# EEZ_DIB_PREL6_r1B2.net
KiCad netlist of a schematic drawn in EAGLE
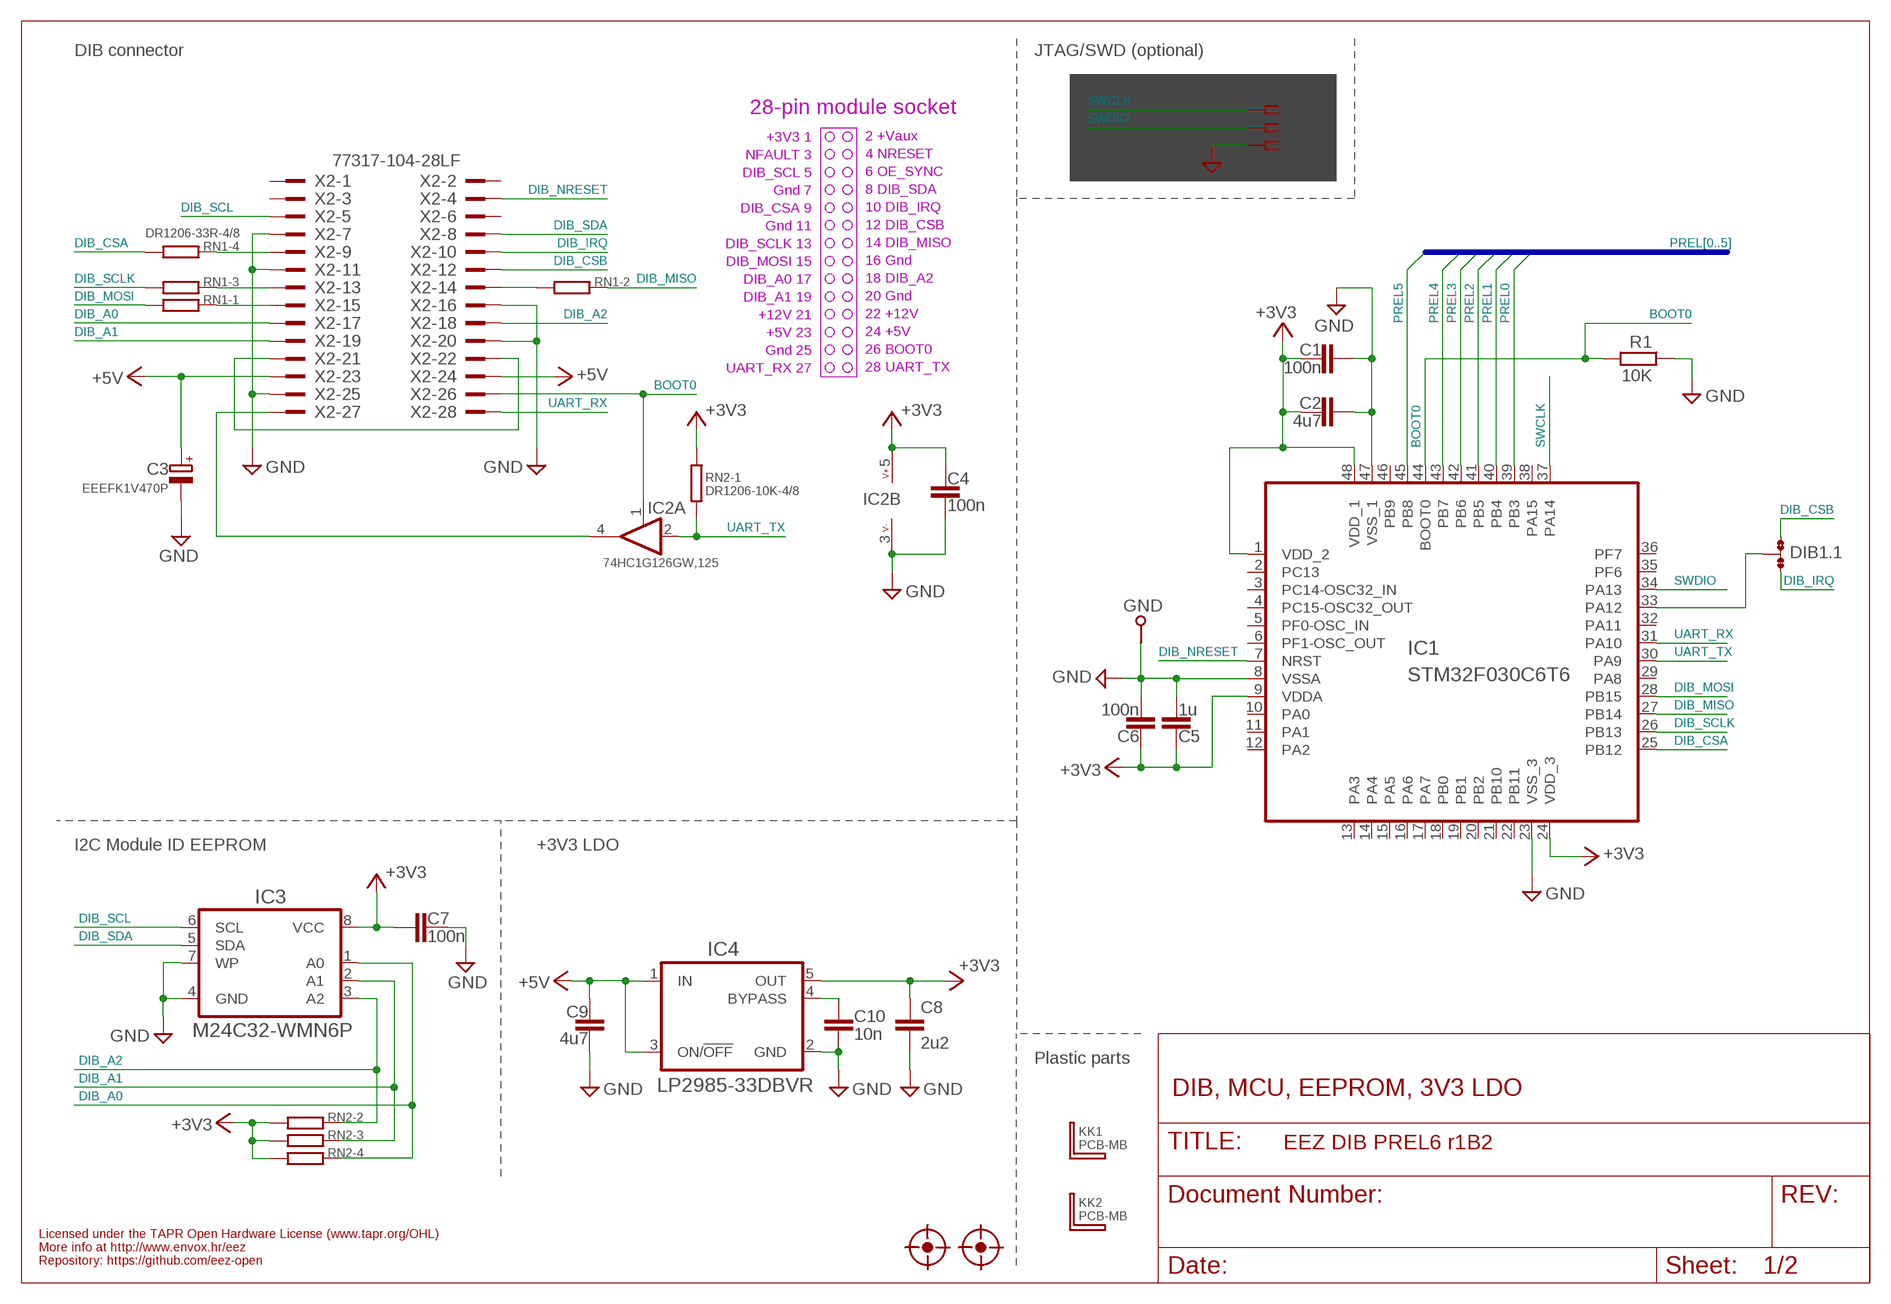
[diagram p0: schematic, sheet 1]
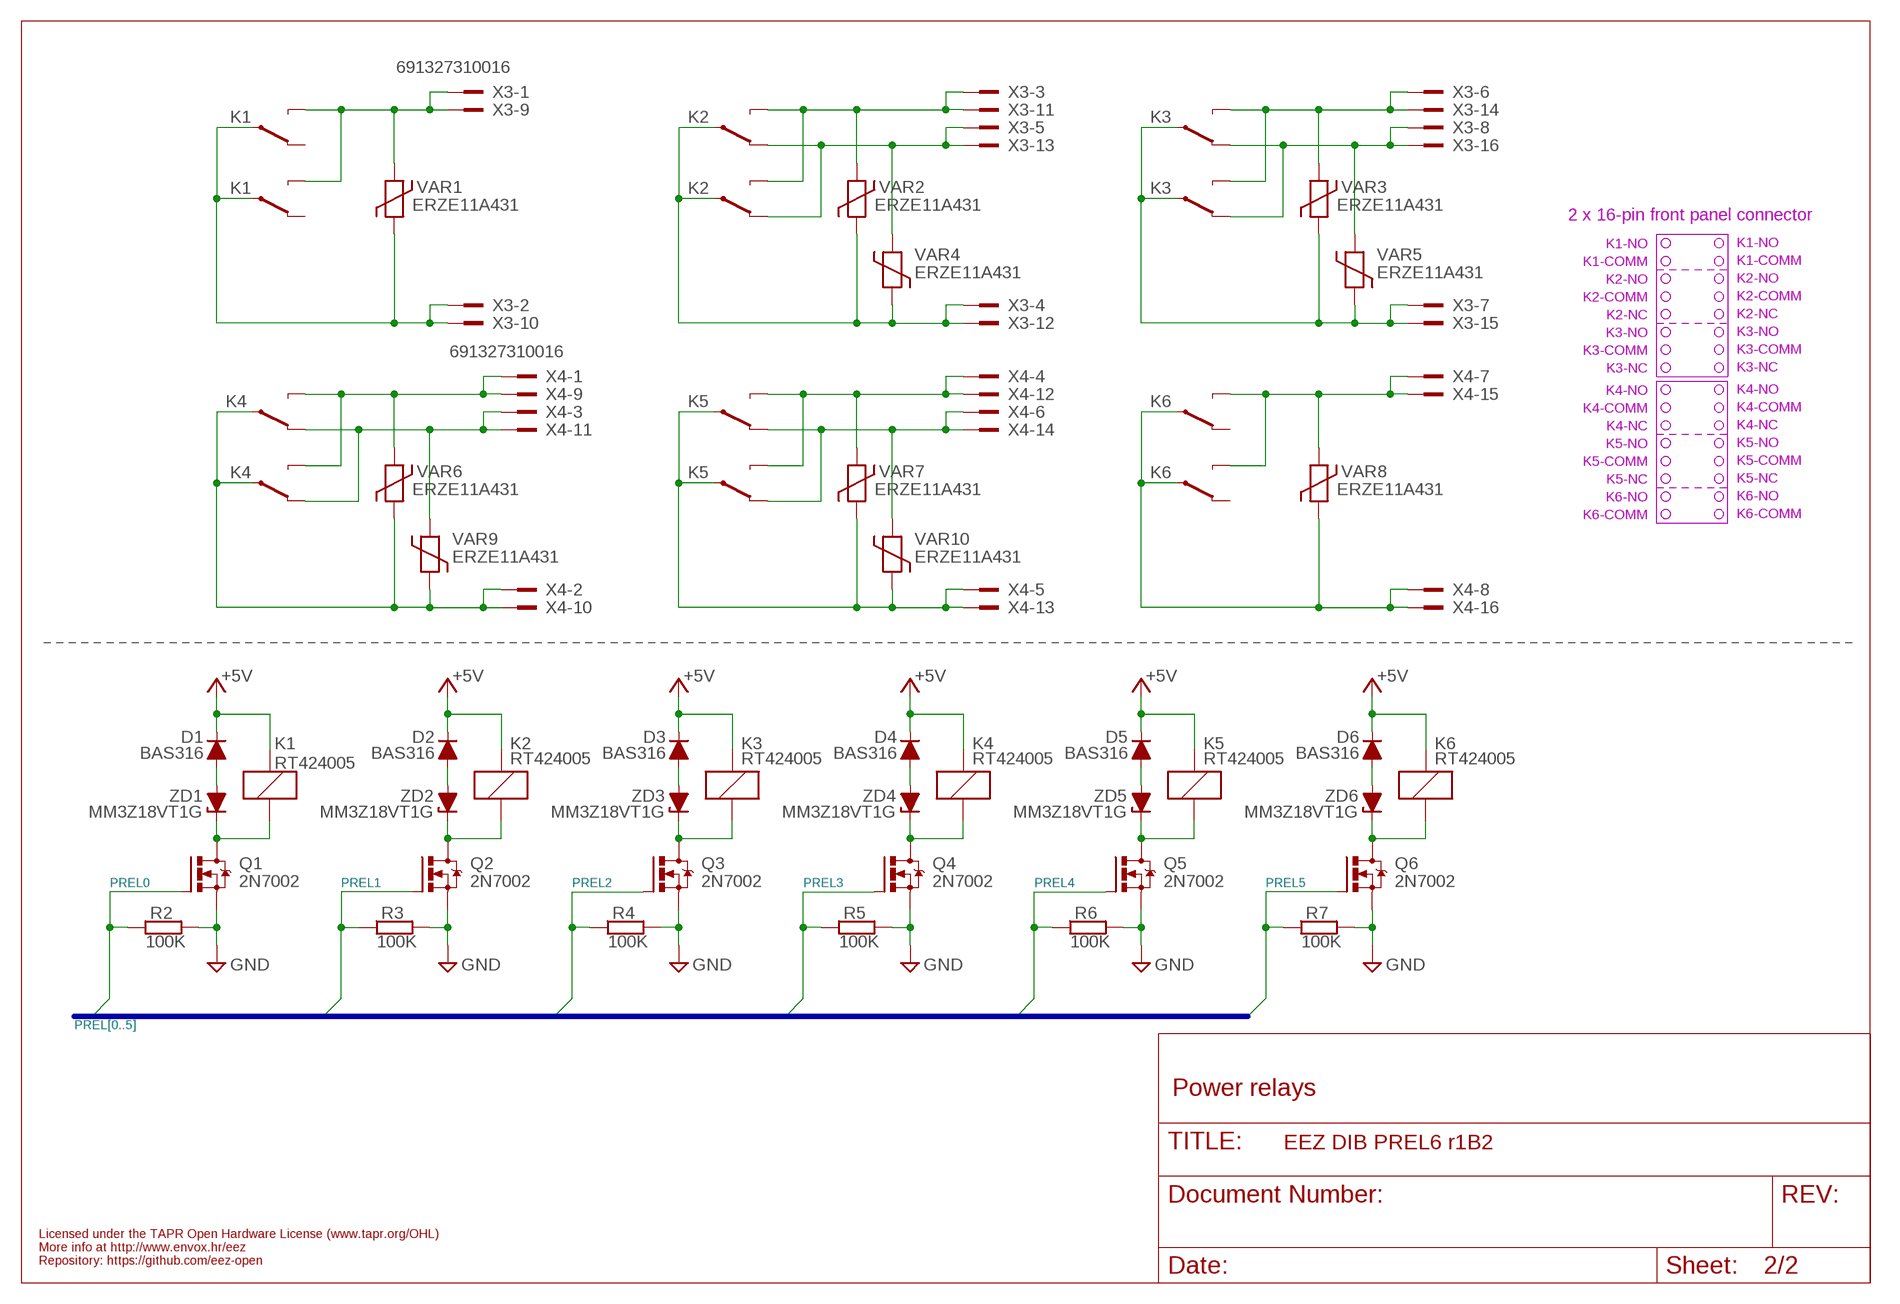
[diagram p1: schematic, sheet 2]

(export (version "E")
  (design (tool "Eeschema 10.0.6"))
  (components
    (comp (ref "D1")
      (value "BAS316")
      (footprint "eagle-import:SOD323-R")
      (libsource (lib "eagle-import") (part "DIODESOD323R"))
    )
    (comp (ref "D2")
      (value "BAS316")
      (footprint "eagle-import:SOD323-R")
      (libsource (lib "eagle-import") (part "DIODESOD323R"))
    )
    (comp (ref "D3")
      (value "BAS316")
      (footprint "eagle-import:SOD323-R")
      (libsource (lib "eagle-import") (part "DIODESOD323R"))
    )
    (comp (ref "D4")
      (value "BAS316")
      (footprint "eagle-import:SOD323-R")
      (libsource (lib "eagle-import") (part "DIODESOD323R"))
    )
    (comp (ref "D5")
      (value "BAS316")
      (footprint "eagle-import:SOD323-R")
      (libsource (lib "eagle-import") (part "DIODESOD323R"))
    )
    (comp (ref "D6")
      (value "BAS316")
      (footprint "eagle-import:SOD323-R")
      (libsource (lib "eagle-import") (part "DIODESOD323R"))
    )
    (comp (ref "K1")
      (value "RT424005")
      (footprint "eagle-import:RT-C_016A5_ROUND")
      (libsource (lib "eagle-import") (part "RELAY_RT314012-2"))
    )
    (comp (ref "K2")
      (value "RT424005")
      (footprint "eagle-import:RT-C_016A5_ROUND")
      (libsource (lib "eagle-import") (part "RELAY_RT314012-2"))
    )
    (comp (ref "K3")
      (value "RT424005")
      (footprint "eagle-import:RT-C_016A5_ROUND")
      (libsource (lib "eagle-import") (part "RELAY_RT314012-2"))
    )
    (comp (ref "K4")
      (value "RT424005")
      (footprint "eagle-import:RT-C_016A5_ROUND")
      (libsource (lib "eagle-import") (part "RELAY_RT314012-2"))
    )
    (comp (ref "K5")
      (value "RT424005")
      (footprint "eagle-import:RT-C_016A5_ROUND")
      (libsource (lib "eagle-import") (part "RELAY_RT314012-2"))
    )
    (comp (ref "K6")
      (value "RT424005")
      (footprint "eagle-import:RT-C_016A5_ROUND")
      (libsource (lib "eagle-import") (part "RELAY_RT314012-2"))
    )
    (comp (ref "Q1")
      (value "2N7002")
      (footprint "eagle-import:SOT103P240X110-3N")
      (fields
        (field (name "MPN") "2N7002-7-F")
        (field (name "MPN_1") "2N7002-7-F")
        (field (name "OC_FARNELL") "1713823")
        (field (name "OC_NEWARK") "25R5679")
        (field (name "PACKAGE") "SOT-23-3")
        (field (name "SUPPLIER") "DIODES INC.")
      )
      (libsource (lib "eagle-import") (part "2N7002"))
    )
    (comp (ref "Q2")
      (value "2N7002")
      (footprint "eagle-import:SOT103P240X110-3N")
      (fields
        (field (name "MPN") "2N7002-7-F")
        (field (name "MPN_1") "2N7002-7-F")
        (field (name "OC_FARNELL") "1713823")
        (field (name "OC_NEWARK") "25R5679")
        (field (name "PACKAGE") "SOT-23-3")
        (field (name "SUPPLIER") "DIODES INC.")
      )
      (libsource (lib "eagle-import") (part "2N7002"))
    )
    (comp (ref "Q3")
      (value "2N7002")
      (footprint "eagle-import:SOT103P240X110-3N")
      (fields
        (field (name "MPN") "2N7002-7-F")
        (field (name "MPN_1") "2N7002-7-F")
        (field (name "OC_FARNELL") "1713823")
        (field (name "OC_NEWARK") "25R5679")
        (field (name "PACKAGE") "SOT-23-3")
        (field (name "SUPPLIER") "DIODES INC.")
      )
      (libsource (lib "eagle-import") (part "2N7002"))
    )
    (comp (ref "Q4")
      (value "2N7002")
      (footprint "eagle-import:SOT103P240X110-3N")
      (fields
        (field (name "MPN") "2N7002-7-F")
        (field (name "MPN_1") "2N7002-7-F")
        (field (name "OC_FARNELL") "1713823")
        (field (name "OC_NEWARK") "25R5679")
        (field (name "PACKAGE") "SOT-23-3")
        (field (name "SUPPLIER") "DIODES INC.")
      )
      (libsource (lib "eagle-import") (part "2N7002"))
    )
    (comp (ref "Q5")
      (value "2N7002")
      (footprint "eagle-import:SOT103P240X110-3N")
      (fields
        (field (name "MPN") "2N7002-7-F")
        (field (name "MPN_1") "2N7002-7-F")
        (field (name "OC_FARNELL") "1713823")
        (field (name "OC_NEWARK") "25R5679")
        (field (name "PACKAGE") "SOT-23-3")
        (field (name "SUPPLIER") "DIODES INC.")
      )
      (libsource (lib "eagle-import") (part "2N7002"))
    )
    (comp (ref "Q6")
      (value "2N7002")
      (footprint "eagle-import:SOT103P240X110-3N")
      (fields
        (field (name "MPN") "2N7002-7-F")
        (field (name "MPN_1") "2N7002-7-F")
        (field (name "OC_FARNELL") "1713823")
        (field (name "OC_NEWARK") "25R5679")
        (field (name "PACKAGE") "SOT-23-3")
        (field (name "SUPPLIER") "DIODES INC.")
      )
      (libsource (lib "eagle-import") (part "2N7002"))
    )
    (comp (ref "R2")
      (value "100K")
      (footprint "eagle-import:R0805")
      (libsource (lib "eagle-import") (part "R-EU_R0805"))
    )
    (comp (ref "R3")
      (value "100K")
      (footprint "eagle-import:R0805")
      (libsource (lib "eagle-import") (part "R-EU_R0805"))
    )
    (comp (ref "R4")
      (value "100K")
      (footprint "eagle-import:R0805")
      (libsource (lib "eagle-import") (part "R-EU_R0805"))
    )
    (comp (ref "R5")
      (value "100K")
      (footprint "eagle-import:R0805")
      (libsource (lib "eagle-import") (part "R-EU_R0805"))
    )
    (comp (ref "R6")
      (value "100K")
      (footprint "eagle-import:R0805")
      (libsource (lib "eagle-import") (part "R-EU_R0805"))
    )
    (comp (ref "R7")
      (value "100K")
      (footprint "eagle-import:R0805")
      (libsource (lib "eagle-import") (part "R-EU_R0805"))
    )
    (comp (ref "VAR1")
      (value "ERZE11A431")
      (footprint "eagle-import:VARISTOR_13MM")
      (libsource (lib "eagle-import") (part "VARISTOR-13"))
    )
    (comp (ref "VAR2")
      (value "ERZE11A431")
      (footprint "eagle-import:VARISTOR_13MM")
      (libsource (lib "eagle-import") (part "VARISTOR-13"))
    )
    (comp (ref "VAR3")
      (value "ERZE11A431")
      (footprint "eagle-import:VARISTOR_13MM")
      (libsource (lib "eagle-import") (part "VARISTOR-13"))
    )
    (comp (ref "VAR4")
      (value "ERZE11A431")
      (footprint "eagle-import:VARISTOR_13MM")
      (libsource (lib "eagle-import") (part "VARISTOR-13"))
    )
    (comp (ref "VAR5")
      (value "ERZE11A431")
      (footprint "eagle-import:VARISTOR_13MM")
      (libsource (lib "eagle-import") (part "VARISTOR-13"))
    )
    (comp (ref "VAR6")
      (value "ERZE11A431")
      (footprint "eagle-import:VARISTOR_13MM")
      (libsource (lib "eagle-import") (part "VARISTOR-13"))
    )
    (comp (ref "VAR7")
      (value "ERZE11A431")
      (footprint "eagle-import:VARISTOR_13MM")
      (libsource (lib "eagle-import") (part "VARISTOR-13"))
    )
    (comp (ref "VAR8")
      (value "ERZE11A431")
      (footprint "eagle-import:VARISTOR_13MM")
      (libsource (lib "eagle-import") (part "VARISTOR-13"))
    )
    (comp (ref "VAR9")
      (value "ERZE11A431")
      (footprint "eagle-import:VARISTOR_13MM")
      (libsource (lib "eagle-import") (part "VARISTOR-13"))
    )
    (comp (ref "VAR10")
      (value "ERZE11A431")
      (footprint "eagle-import:VARISTOR_13MM")
      (libsource (lib "eagle-import") (part "VARISTOR-13"))
    )
    (comp (ref "X3")
      (value "691327310016")
      (footprint "eagle-import:691327310016")
      (libsource (lib "eagle-import") (part "691327310016"))
    )
    (comp (ref "X4")
      (value "691327310016")
      (footprint "eagle-import:691327310016")
      (libsource (lib "eagle-import") (part "691327310016"))
    )
    (comp (ref "ZD1")
      (value "MM3Z18VT1G")
      (footprint "eagle-import:SOD323-R")
      (libsource (lib "eagle-import") (part "ZENER-DIODESOD323R"))
    )
    (comp (ref "ZD2")
      (value "MM3Z18VT1G")
      (footprint "eagle-import:SOD323-R")
      (libsource (lib "eagle-import") (part "ZENER-DIODESOD323R"))
    )
    (comp (ref "ZD3")
      (value "MM3Z18VT1G")
      (footprint "eagle-import:SOD323-R")
      (libsource (lib "eagle-import") (part "ZENER-DIODESOD323R"))
    )
    (comp (ref "ZD4")
      (value "MM3Z18VT1G")
      (footprint "eagle-import:SOD323-R")
      (libsource (lib "eagle-import") (part "ZENER-DIODESOD323R"))
    )
    (comp (ref "ZD5")
      (value "MM3Z18VT1G")
      (footprint "eagle-import:SOD323-R")
      (libsource (lib "eagle-import") (part "ZENER-DIODESOD323R"))
    )
    (comp (ref "ZD6")
      (value "MM3Z18VT1G")
      (footprint "eagle-import:SOD323-R")
      (libsource (lib "eagle-import") (part "ZENER-DIODESOD323R"))
    )
    (comp (ref "C1")
      (value "100n")
      (footprint "eagle-import:C0603")
      (libsource (lib "eagle-import") (part "C-EUC0603"))
    )
    (comp (ref "C2")
      (value "4u7")
      (footprint "eagle-import:C0805")
      (libsource (lib "eagle-import") (part "C-EUC0805"))
    )
    (comp (ref "C3")
      (value "EEEFK1V470P")
      (footprint "eagle-import:CAPAE660X610N")
      (libsource (lib "eagle-import") (part "ECAPPANASONIC_H"))
    )
    (comp (ref "C4")
      (value "100n")
      (footprint "eagle-import:C0603")
      (libsource (lib "eagle-import") (part "C-EUC0603"))
    )
    (comp (ref "C5")
      (value "1u")
      (footprint "eagle-import:C0805")
      (libsource (lib "eagle-import") (part "C-EUC0805"))
    )
    (comp (ref "C6")
      (value "100n")
      (footprint "eagle-import:C0603")
      (libsource (lib "eagle-import") (part "C-EUC0603"))
    )
    (comp (ref "C7")
      (value "100n")
      (footprint "eagle-import:C0603")
      (libsource (lib "eagle-import") (part "C-EUC0603"))
    )
    (comp (ref "C8")
      (value "2u2")
      (footprint "eagle-import:C0805")
      (libsource (lib "eagle-import") (part "C-EUC0805"))
    )
    (comp (ref "C9")
      (value "4u7")
      (footprint "eagle-import:C0805")
      (libsource (lib "eagle-import") (part "C-EUC0805"))
    )
    (comp (ref "C10")
      (value "10n")
      (footprint "eagle-import:C0805")
      (libsource (lib "eagle-import") (part "C-EUC0805"))
    )
    (comp (ref "DIB1.1")
      (value "JP3-CUT-0805-ROTATED")
      (footprint "eagle-import:JP3-0805-CUT2")
      (libsource (lib "eagle-import") (part "JP3-CUT-0805-ROTATED"))
    )
    (comp (ref "FM1")
      (value "FIDUCIAL_2")
      (footprint "eagle-import:FIDUCIAL_DUAL")
      (libsource (lib "eagle-import") (part "FIDUCIAL_2"))
    )
    (comp (ref "FM2")
      (value "FIDUCIAL_2")
      (footprint "eagle-import:FIDUCIAL_DUAL")
      (libsource (lib "eagle-import") (part "FIDUCIAL_2"))
    )
    (comp (ref "GND")
      (value "PCB_TEST_TABSHIELD")
      (footprint "eagle-import:PCB_SHIELD_TAB")
      (libsource (lib "eagle-import") (part "PCB_TEST_TABSHIELD"))
    )
    (comp (ref "IC1")
      (value "STM32F030C6T6")
      (footprint "eagle-import:LQFP-48")
      (libsource (lib "eagle-import") (part "STM32F030C6T6"))
    )
    (comp (ref "IC2")
      (value "74HC1G126GW,125")
      (footprint "eagle-import:SOT65P210X110-5N")
      (libsource (lib "eagle-import") (part "74HC1G126GW,125"))
    )
    (comp (ref "IC3")
      (value "M24C32-WMN6P")
      (footprint "eagle-import:SOIC127P600X173-8N")
      (libsource (lib "eagle-import") (part "AT24CXXSOIC8"))
    )
    (comp (ref "IC4")
      (value "LP2985-33DBVR")
      (footprint "eagle-import:SOT95P270X145-5N")
      (libsource (lib "eagle-import") (part "LP2985"))
    )
    (comp (ref "KK1")
      (value "PCB-MB")
      (footprint "eagle-import:PCB-MB")
      (libsource (lib "eagle-import") (part "PCB-MB"))
    )
    (comp (ref "KK2")
      (value "PCB-MB")
      (footprint "eagle-import:PCB-MB")
      (libsource (lib "eagle-import") (part "PCB-MB"))
    )
    (comp (ref "R1")
      (value "10K")
      (footprint "eagle-import:R0805")
      (libsource (lib "eagle-import") (part "R-EU_R0805"))
    )
    (comp (ref "RN1")
      (value "DR1206-33R-4/8")
      (footprint "eagle-import:CAY16")
      (libsource (lib "eagle-import") (part "R_ARRAY4"))
    )
    (comp (ref "RN2")
      (value "DR1206-10K-4/8")
      (footprint "eagle-import:CAY16")
      (libsource (lib "eagle-import") (part "R_ARRAY4"))
    )
    (comp (ref "X1")
      (value "SSW-106-02-S-S")
      (footprint "eagle-import:SSW-106-02-S-S")
      (libsource (lib "eagle-import") (part "SSW-106-02-S-S"))
    )
    (comp (ref "X2")
      (value "77317-104-28LF")
      (footprint "eagle-import:77317-104-28LF")
      (libsource (lib "eagle-import") (part "77317-104-28LF"))
    )
  )
  (nets
    (net (code "1") (name "+3V3") (class "Default")
      (node (ref "C1") (pin "2") (pinfunction "2_2") (pintype "passive"))
      (node (ref "C2") (pin "1") (pinfunction "1_1") (pintype "passive"))
      (node (ref "C4") (pin "1") (pinfunction "1_1") (pintype "passive"))
      (node (ref "C5") (pin "2") (pinfunction "2_2") (pintype "passive"))
      (node (ref "C6") (pin "1") (pinfunction "1_1") (pintype "passive"))
      (node (ref "C7") (pin "2") (pinfunction "2_2") (pintype "passive"))
      (node (ref "C8") (pin "1") (pinfunction "1_1") (pintype "passive"))
      (node (ref "IC1") (pin "1") (pinfunction "VDD_2_1") (pintype "passive"))
      (node (ref "IC1") (pin "24") (pinfunction "VDD_3_24") (pintype "passive"))
      (node (ref "IC1") (pin "48") (pinfunction "VDD_1_48") (pintype "passive"))
      (node (ref "IC1") (pin "9") (pinfunction "VDDA_9") (pintype "passive"))
      (node (ref "IC2") (pin "5") (pinfunction "V+_5") (pintype "power_in"))
      (node (ref "IC3") (pin "8") (pinfunction "VCC_8") (pintype "power_in"))
      (node (ref "IC4") (pin "5") (pinfunction "OUT_5") (pintype "passive"))
      (node (ref "RN2") (pin "5") (pinfunction "2_5") (pintype "passive"))
      (node (ref "RN2") (pin "6") (pinfunction "2_6") (pintype "passive"))
      (node (ref "RN2") (pin "7") (pinfunction "2_7") (pintype "passive"))
      (node (ref "RN2") (pin "8") (pinfunction "2_8") (pintype "passive"))
    )
    (net (code "2") (name "+5V") (class "Default")
      (node (ref "C3") (pin "1") (pinfunction "+_1") (pintype "passive"))
      (node (ref "C9") (pin "2") (pinfunction "2_2") (pintype "passive"))
      (node (ref "D1") (pin "C") (pinfunction "C_C") (pintype "passive"))
      (node (ref "D2") (pin "C") (pinfunction "C_C") (pintype "passive"))
      (node (ref "D3") (pin "C") (pinfunction "C_C") (pintype "passive"))
      (node (ref "D4") (pin "C") (pinfunction "C_C") (pintype "passive"))
      (node (ref "D5") (pin "C") (pinfunction "C_C") (pintype "passive"))
      (node (ref "D6") (pin "C") (pinfunction "C_C") (pintype "passive"))
      (node (ref "IC4") (pin "1") (pinfunction "IN_1") (pintype "input"))
      (node (ref "IC4") (pin "3") (pinfunction "ON/~{OFF}_3") (pintype "input"))
      (node (ref "K1") (pin "A2") (pinfunction "C1_A2") (pintype "passive"))
      (node (ref "K2") (pin "A2") (pinfunction "C1_A2") (pintype "passive"))
      (node (ref "K3") (pin "A2") (pinfunction "C1_A2") (pintype "passive"))
      (node (ref "K4") (pin "A2") (pinfunction "C1_A2") (pintype "passive"))
      (node (ref "K5") (pin "A2") (pinfunction "C1_A2") (pintype "passive"))
      (node (ref "K6") (pin "A2") (pinfunction "C1_A2") (pintype "passive"))
      (node (ref "X2") (pin "23") (pinfunction "1_23") (pintype "passive"))
      (node (ref "X2") (pin "24") (pinfunction "1_24") (pintype "passive"))
    )
    (net (code "5") (name "BOOT0") (class "Default")
      (node (ref "IC1") (pin "44") (pinfunction "BOOT0_44") (pintype "input"))
      (node (ref "IC2") (pin "1") (pinfunction "EN_1") (pintype "input"))
      (node (ref "R1") (pin "2") (pinfunction "2_2") (pintype "passive"))
      (node (ref "X2") (pin "26") (pinfunction "1_26") (pintype "passive"))
    )
    (net (code "6") (name "DIB_A0") (class "Default")
      (node (ref "IC3") (pin "1") (pinfunction "A0_1") (pintype "input"))
      (node (ref "RN2") (pin "4") (pinfunction "1_4") (pintype "passive"))
      (node (ref "X2") (pin "17") (pinfunction "1_17") (pintype "passive"))
    )
    (net (code "7") (name "DIB_A1") (class "Default")
      (node (ref "IC3") (pin "2") (pinfunction "A1_2") (pintype "input"))
      (node (ref "RN2") (pin "3") (pinfunction "1_3") (pintype "passive"))
      (node (ref "X2") (pin "19") (pinfunction "1_19") (pintype "passive"))
    )
    (net (code "8") (name "DIB_A2") (class "Default")
      (node (ref "IC3") (pin "3") (pinfunction "A2_3") (pintype "input"))
      (node (ref "RN2") (pin "2") (pinfunction "1_2") (pintype "passive"))
      (node (ref "X2") (pin "18") (pinfunction "1_18") (pintype "passive"))
    )
    (net (code "9") (name "DIB_CSA") (class "Default")
      (node (ref "IC1") (pin "25") (pinfunction "PB12_25") (pintype "bidirectional"))
      (node (ref "RN1") (pin "4") (pinfunction "1_4") (pintype "passive"))
    )
    (net (code "10") (name "DIB_CSB") (class "Default")
      (node (ref "DIB1.1") (pin "NO") (pinfunction "NO_NO") (pintype "passive"))
      (node (ref "X2") (pin "12") (pinfunction "1_12") (pintype "passive"))
    )
    (net (code "11") (name "DIB_IRQ") (class "Default")
      (node (ref "DIB1.1") (pin "NC") (pinfunction "NC_NC") (pintype "passive"))
      (node (ref "X2") (pin "10") (pinfunction "1_10") (pintype "passive"))
    )
    (net (code "12") (name "DIB_MISO") (class "Default")
      (node (ref "IC1") (pin "27") (pinfunction "PB14_27") (pintype "bidirectional"))
      (node (ref "RN1") (pin "2") (pinfunction "1_2") (pintype "passive"))
    )
    (net (code "13") (name "DIB_MOSI") (class "Default")
      (node (ref "IC1") (pin "28") (pinfunction "PB15_28") (pintype "bidirectional"))
      (node (ref "RN1") (pin "1") (pinfunction "1_1") (pintype "passive"))
    )
    (net (code "14") (name "DIB_NRESET") (class "Default")
      (node (ref "IC1") (pin "7") (pinfunction "NRST_7") (pintype "input"))
      (node (ref "X2") (pin "4") (pinfunction "1_4") (pintype "passive"))
    )
    (net (code "15") (name "DIB_SCL") (class "Default")
      (node (ref "IC3") (pin "6") (pinfunction "SCL_6") (pintype "bidirectional"))
      (node (ref "X2") (pin "5") (pinfunction "1_5") (pintype "passive"))
    )
    (net (code "16") (name "DIB_SCLK") (class "Default")
      (node (ref "IC1") (pin "26") (pinfunction "PB13_26") (pintype "bidirectional"))
      (node (ref "RN1") (pin "3") (pinfunction "1_3") (pintype "passive"))
    )
    (net (code "17") (name "DIB_SDA") (class "Default")
      (node (ref "IC3") (pin "5") (pinfunction "SDA_5") (pintype "bidirectional"))
      (node (ref "X2") (pin "8") (pinfunction "1_8") (pintype "passive"))
    )
    (net (code "18") (name "GND") (class "Default")
      (node (ref "C1") (pin "1") (pinfunction "1_1") (pintype "passive"))
      (node (ref "C10") (pin "1") (pinfunction "1_1") (pintype "passive"))
      (node (ref "C2") (pin "2") (pinfunction "2_2") (pintype "passive"))
      (node (ref "C3") (pin "2") (pinfunction "-_2") (pintype "passive"))
      (node (ref "C4") (pin "2") (pinfunction "2_2") (pintype "passive"))
      (node (ref "C5") (pin "1") (pinfunction "1_1") (pintype "passive"))
      (node (ref "C6") (pin "2") (pinfunction "2_2") (pintype "passive"))
      (node (ref "C7") (pin "1") (pinfunction "1_1") (pintype "passive"))
      (node (ref "C8") (pin "2") (pinfunction "2_2") (pintype "passive"))
      (node (ref "C9") (pin "1") (pinfunction "1_1") (pintype "passive"))
      (node (ref "GND") (pin "1") (pinfunction "P$1_1") (pintype "bidirectional"))
      (node (ref "IC1") (pin "23") (pinfunction "VSS_3_23") (pintype "passive"))
      (node (ref "IC1") (pin "47") (pinfunction "VSS_1_47") (pintype "passive"))
      (node (ref "IC1") (pin "8") (pinfunction "VSSA_8") (pintype "passive"))
      (node (ref "IC2") (pin "3") (pinfunction "V-_3") (pintype "power_in"))
      (node (ref "IC3") (pin "4") (pinfunction "GND_4") (pintype "passive"))
      (node (ref "IC3") (pin "7") (pinfunction "WP_7") (pintype "input"))
      (node (ref "IC4") (pin "2") (pinfunction "GND_2") (pintype "passive"))
      (node (ref "Q1") (pin "2") (pinfunction "S_2") (pintype "passive"))
      (node (ref "Q2") (pin "2") (pinfunction "S_2") (pintype "passive"))
      (node (ref "Q3") (pin "2") (pinfunction "S_2") (pintype "passive"))
      (node (ref "Q4") (pin "2") (pinfunction "S_2") (pintype "passive"))
      (node (ref "Q5") (pin "2") (pinfunction "S_2") (pintype "passive"))
      (node (ref "Q6") (pin "2") (pinfunction "S_2") (pintype "passive"))
      (node (ref "R1") (pin "1") (pinfunction "1_1") (pintype "passive"))
      (node (ref "R2") (pin "2") (pinfunction "2_2") (pintype "passive"))
      (node (ref "R3") (pin "2") (pinfunction "2_2") (pintype "passive"))
      (node (ref "R4") (pin "2") (pinfunction "2_2") (pintype "passive"))
      (node (ref "R5") (pin "2") (pinfunction "2_2") (pintype "passive"))
      (node (ref "R6") (pin "2") (pinfunction "2_2") (pintype "passive"))
      (node (ref "R7") (pin "2") (pinfunction "2_2") (pintype "passive"))
      (node (ref "X1") (pin "3") (pinfunction "1_3") (pintype "passive"))
      (node (ref "X2") (pin "11") (pinfunction "1_11") (pintype "passive"))
      (node (ref "X2") (pin "16") (pinfunction "1_16") (pintype "passive"))
      (node (ref "X2") (pin "20") (pinfunction "1_20") (pintype "passive"))
      (node (ref "X2") (pin "25") (pinfunction "1_25") (pintype "passive"))
      (node (ref "X2") (pin "7") (pinfunction "1_7") (pintype "passive"))
    )
    (net (code "19") (name "Net-(D1-PadA)") (class "Default")
      (node (ref "D1") (pin "A") (pinfunction "A_A") (pintype "passive"))
      (node (ref "ZD1") (pin "A") (pinfunction "A_A") (pintype "passive"))
    )
    (net (code "20") (name "Net-(D2-PadA)") (class "Default")
      (node (ref "D2") (pin "A") (pinfunction "A_A") (pintype "passive"))
      (node (ref "ZD2") (pin "A") (pinfunction "A_A") (pintype "passive"))
    )
    (net (code "21") (name "Net-(D3-PadA)") (class "Default")
      (node (ref "D3") (pin "A") (pinfunction "A_A") (pintype "passive"))
      (node (ref "ZD3") (pin "A") (pinfunction "A_A") (pintype "passive"))
    )
    (net (code "22") (name "Net-(D4-PadA)") (class "Default")
      (node (ref "D4") (pin "A") (pinfunction "A_A") (pintype "passive"))
      (node (ref "ZD4") (pin "A") (pinfunction "A_A") (pintype "passive"))
    )
    (net (code "23") (name "Net-(D5-PadA)") (class "Default")
      (node (ref "D5") (pin "A") (pinfunction "A_A") (pintype "passive"))
      (node (ref "ZD5") (pin "A") (pinfunction "A_A") (pintype "passive"))
    )
    (net (code "24") (name "Net-(D6-PadA)") (class "Default")
      (node (ref "D6") (pin "A") (pinfunction "A_A") (pintype "passive"))
      (node (ref "ZD6") (pin "A") (pinfunction "A_A") (pintype "passive"))
    )
    (net (code "25") (name "Net-(IC1-PA12)") (class "Default")
      (node (ref "DIB1.1") (pin "COM") (pinfunction "COM_COM") (pintype "passive"))
      (node (ref "IC1") (pin "33") (pinfunction "PA12_33") (pintype "bidirectional"))
    )
    (net (code "26") (name "Net-(IC2A-O)") (class "Default")
      (node (ref "IC2") (pin "4") (pinfunction "O_4") (pintype "output"))
      (node (ref "X2") (pin "27") (pinfunction "1_27") (pintype "passive"))
    )
    (net (code "27") (name "Net-(IC4-BYPASS)") (class "Default")
      (node (ref "C10") (pin "2") (pinfunction "2_2") (pintype "passive"))
      (node (ref "IC4") (pin "4") (pinfunction "BYPASS_4") (pintype "passive"))
    )
    (net (code "28") (name "Net-(K1A-O)") (class "Default")
      (node (ref "K1") (pin "14A") (pinfunction "O_14A") (pintype "passive"))
      (node (ref "K1") (pin "14B") (pinfunction "O_14B") (pintype "passive"))
      (node (ref "VAR1") (pin "2") (pinfunction "P$2_2") (pintype "bidirectional"))
      (node (ref "X3") (pin "1") (pinfunction "1_1") (pintype "passive"))
      (node (ref "X3") (pin "9") (pinfunction "1_9") (pintype "passive"))
    )
    (net (code "29") (name "Net-(K1A-P)") (class "Default")
      (node (ref "K1") (pin "11A") (pinfunction "P_11A") (pintype "passive"))
      (node (ref "K1") (pin "11B") (pinfunction "P_11B") (pintype "passive"))
      (node (ref "VAR1") (pin "1") (pinfunction "P$1_1") (pintype "bidirectional"))
      (node (ref "X3") (pin "10") (pinfunction "1_10") (pintype "passive"))
      (node (ref "X3") (pin "2") (pinfunction "1_2") (pintype "passive"))
    )
    (net (code "30") (name "Net-(K1C-C2)") (class "Default")
      (node (ref "K1") (pin "A1") (pinfunction "C2_A1") (pintype "passive"))
      (node (ref "Q1") (pin "3") (pinfunction "D_3") (pintype "passive"))
      (node (ref "ZD1") (pin "C") (pinfunction "C_C") (pintype "passive"))
    )
    (net (code "31") (name "Net-(K2A-O)") (class "Default")
      (node (ref "K2") (pin "14A") (pinfunction "O_14A") (pintype "passive"))
      (node (ref "K2") (pin "14B") (pinfunction "O_14B") (pintype "passive"))
      (node (ref "VAR2") (pin "2") (pinfunction "P$2_2") (pintype "bidirectional"))
      (node (ref "X3") (pin "11") (pinfunction "1_11") (pintype "passive"))
      (node (ref "X3") (pin "3") (pinfunction "1_3") (pintype "passive"))
    )
    (net (code "32") (name "Net-(K2A-P)") (class "Default")
      (node (ref "K2") (pin "11A") (pinfunction "P_11A") (pintype "passive"))
      (node (ref "K2") (pin "11B") (pinfunction "P_11B") (pintype "passive"))
      (node (ref "VAR2") (pin "1") (pinfunction "P$1_1") (pintype "bidirectional"))
      (node (ref "VAR4") (pin "1") (pinfunction "P$1_1") (pintype "bidirectional"))
      (node (ref "X3") (pin "12") (pinfunction "1_12") (pintype "passive"))
      (node (ref "X3") (pin "4") (pinfunction "1_4") (pintype "passive"))
    )
    (net (code "33") (name "Net-(K2A-S)") (class "Default")
      (node (ref "K2") (pin "12A") (pinfunction "S_12A") (pintype "passive"))
      (node (ref "K2") (pin "12B") (pinfunction "S_12B") (pintype "passive"))
      (node (ref "VAR4") (pin "2") (pinfunction "P$2_2") (pintype "bidirectional"))
      (node (ref "X3") (pin "13") (pinfunction "1_13") (pintype "passive"))
      (node (ref "X3") (pin "5") (pinfunction "1_5") (pintype "passive"))
    )
    (net (code "34") (name "Net-(K2C-C2)") (class "Default")
      (node (ref "K2") (pin "A1") (pinfunction "C2_A1") (pintype "passive"))
      (node (ref "Q2") (pin "3") (pinfunction "D_3") (pintype "passive"))
      (node (ref "ZD2") (pin "C") (pinfunction "C_C") (pintype "passive"))
    )
    (net (code "35") (name "Net-(K3A-O)") (class "Default")
      (node (ref "K3") (pin "14A") (pinfunction "O_14A") (pintype "passive"))
      (node (ref "K3") (pin "14B") (pinfunction "O_14B") (pintype "passive"))
      (node (ref "VAR3") (pin "2") (pinfunction "P$2_2") (pintype "bidirectional"))
      (node (ref "X3") (pin "14") (pinfunction "1_14") (pintype "passive"))
      (node (ref "X3") (pin "6") (pinfunction "1_6") (pintype "passive"))
    )
    (net (code "36") (name "Net-(K3A-P)") (class "Default")
      (node (ref "K3") (pin "11A") (pinfunction "P_11A") (pintype "passive"))
      (node (ref "K3") (pin "11B") (pinfunction "P_11B") (pintype "passive"))
      (node (ref "VAR3") (pin "1") (pinfunction "P$1_1") (pintype "bidirectional"))
      (node (ref "VAR5") (pin "1") (pinfunction "P$1_1") (pintype "bidirectional"))
      (node (ref "X3") (pin "15") (pinfunction "1_15") (pintype "passive"))
      (node (ref "X3") (pin "7") (pinfunction "1_7") (pintype "passive"))
    )
    (net (code "37") (name "Net-(K3A-S)") (class "Default")
      (node (ref "K3") (pin "12A") (pinfunction "S_12A") (pintype "passive"))
      (node (ref "K3") (pin "12B") (pinfunction "S_12B") (pintype "passive"))
      (node (ref "VAR5") (pin "2") (pinfunction "P$2_2") (pintype "bidirectional"))
      (node (ref "X3") (pin "16") (pinfunction "1_16") (pintype "passive"))
      (node (ref "X3") (pin "8") (pinfunction "1_8") (pintype "passive"))
    )
    (net (code "38") (name "Net-(K3C-C2)") (class "Default")
      (node (ref "K3") (pin "A1") (pinfunction "C2_A1") (pintype "passive"))
      (node (ref "Q3") (pin "3") (pinfunction "D_3") (pintype "passive"))
      (node (ref "ZD3") (pin "C") (pinfunction "C_C") (pintype "passive"))
    )
    (net (code "39") (name "Net-(K4A-O)") (class "Default")
      (node (ref "K4") (pin "14A") (pinfunction "O_14A") (pintype "passive"))
      (node (ref "K4") (pin "14B") (pinfunction "O_14B") (pintype "passive"))
      (node (ref "VAR6") (pin "2") (pinfunction "P$2_2") (pintype "bidirectional"))
      (node (ref "X4") (pin "1") (pinfunction "1_1") (pintype "passive"))
      (node (ref "X4") (pin "9") (pinfunction "1_9") (pintype "passive"))
    )
    (net (code "40") (name "Net-(K4A-P)") (class "Default")
      (node (ref "K4") (pin "11A") (pinfunction "P_11A") (pintype "passive"))
      (node (ref "K4") (pin "11B") (pinfunction "P_11B") (pintype "passive"))
      (node (ref "VAR6") (pin "1") (pinfunction "P$1_1") (pintype "bidirectional"))
      (node (ref "VAR9") (pin "1") (pinfunction "P$1_1") (pintype "bidirectional"))
      (node (ref "X4") (pin "10") (pinfunction "1_10") (pintype "passive"))
      (node (ref "X4") (pin "2") (pinfunction "1_2") (pintype "passive"))
    )
    (net (code "41") (name "Net-(K4A-S)") (class "Default")
      (node (ref "K4") (pin "12A") (pinfunction "S_12A") (pintype "passive"))
      (node (ref "K4") (pin "12B") (pinfunction "S_12B") (pintype "passive"))
      (node (ref "VAR9") (pin "2") (pinfunction "P$2_2") (pintype "bidirectional"))
      (node (ref "X4") (pin "11") (pinfunction "1_11") (pintype "passive"))
      (node (ref "X4") (pin "3") (pinfunction "1_3") (pintype "passive"))
    )
    (net (code "42") (name "Net-(K4C-C2)") (class "Default")
      (node (ref "K4") (pin "A1") (pinfunction "C2_A1") (pintype "passive"))
      (node (ref "Q4") (pin "3") (pinfunction "D_3") (pintype "passive"))
      (node (ref "ZD4") (pin "C") (pinfunction "C_C") (pintype "passive"))
    )
    (net (code "43") (name "Net-(K5A-O)") (class "Default")
      (node (ref "K5") (pin "14A") (pinfunction "O_14A") (pintype "passive"))
      (node (ref "K5") (pin "14B") (pinfunction "O_14B") (pintype "passive"))
      (node (ref "VAR7") (pin "2") (pinfunction "P$2_2") (pintype "bidirectional"))
      (node (ref "X4") (pin "12") (pinfunction "1_12") (pintype "passive"))
      (node (ref "X4") (pin "4") (pinfunction "1_4") (pintype "passive"))
    )
    (net (code "44") (name "Net-(K5A-P)") (class "Default")
      (node (ref "K5") (pin "11A") (pinfunction "P_11A") (pintype "passive"))
      (node (ref "K5") (pin "11B") (pinfunction "P_11B") (pintype "passive"))
      (node (ref "VAR10") (pin "1") (pinfunction "P$1_1") (pintype "bidirectional"))
      (node (ref "VAR7") (pin "1") (pinfunction "P$1_1") (pintype "bidirectional"))
      (node (ref "X4") (pin "13") (pinfunction "1_13") (pintype "passive"))
      (node (ref "X4") (pin "5") (pinfunction "1_5") (pintype "passive"))
    )
    (net (code "45") (name "Net-(K5A-S)") (class "Default")
      (node (ref "K5") (pin "12A") (pinfunction "S_12A") (pintype "passive"))
      (node (ref "K5") (pin "12B") (pinfunction "S_12B") (pintype "passive"))
      (node (ref "VAR10") (pin "2") (pinfunction "P$2_2") (pintype "bidirectional"))
      (node (ref "X4") (pin "14") (pinfunction "1_14") (pintype "passive"))
      (node (ref "X4") (pin "6") (pinfunction "1_6") (pintype "passive"))
    )
    (net (code "46") (name "Net-(K5C-C2)") (class "Default")
      (node (ref "K5") (pin "A1") (pinfunction "C2_A1") (pintype "passive"))
      (node (ref "Q5") (pin "3") (pinfunction "D_3") (pintype "passive"))
      (node (ref "ZD5") (pin "C") (pinfunction "C_C") (pintype "passive"))
    )
    (net (code "47") (name "Net-(K6A-O)") (class "Default")
      (node (ref "K6") (pin "14A") (pinfunction "O_14A") (pintype "passive"))
      (node (ref "K6") (pin "14B") (pinfunction "O_14B") (pintype "passive"))
      (node (ref "VAR8") (pin "2") (pinfunction "P$2_2") (pintype "bidirectional"))
      (node (ref "X4") (pin "15") (pinfunction "1_15") (pintype "passive"))
      (node (ref "X4") (pin "7") (pinfunction "1_7") (pintype "passive"))
    )
    (net (code "48") (name "Net-(K6A-P)") (class "Default")
      (node (ref "K6") (pin "11A") (pinfunction "P_11A") (pintype "passive"))
      (node (ref "K6") (pin "11B") (pinfunction "P_11B") (pintype "passive"))
      (node (ref "VAR8") (pin "1") (pinfunction "P$1_1") (pintype "bidirectional"))
      (node (ref "X4") (pin "16") (pinfunction "1_16") (pintype "passive"))
      (node (ref "X4") (pin "8") (pinfunction "1_8") (pintype "passive"))
    )
    (net (code "49") (name "Net-(K6C-C2)") (class "Default")
      (node (ref "K6") (pin "A1") (pinfunction "C2_A1") (pintype "passive"))
      (node (ref "Q6") (pin "3") (pinfunction "D_3") (pintype "passive"))
      (node (ref "ZD6") (pin "C") (pinfunction "C_C") (pintype "passive"))
    )
    (net (code "50") (name "Net-(RN1A-2)") (class "Default")
      (node (ref "RN1") (pin "8") (pinfunction "2_8") (pintype "passive"))
      (node (ref "X2") (pin "15") (pinfunction "1_15") (pintype "passive"))
    )
    (net (code "51") (name "Net-(RN1B-2)") (class "Default")
      (node (ref "RN1") (pin "7") (pinfunction "2_7") (pintype "passive"))
      (node (ref "X2") (pin "14") (pinfunction "1_14") (pintype "passive"))
    )
    (net (code "52") (name "Net-(RN1C-2)") (class "Default")
      (node (ref "RN1") (pin "6") (pinfunction "2_6") (pintype "passive"))
      (node (ref "X2") (pin "13") (pinfunction "1_13") (pintype "passive"))
    )
    (net (code "53") (name "Net-(RN1D-2)") (class "Default")
      (node (ref "RN1") (pin "5") (pinfunction "2_5") (pintype "passive"))
      (node (ref "X2") (pin "9") (pinfunction "1_9") (pintype "passive"))
    )
    (net (code "54") (name "Net-(X2N-1)") (class "Default")
      (node (ref "X2") (pin "21") (pinfunction "1_21") (pintype "passive"))
      (node (ref "X2") (pin "22") (pinfunction "1_22") (pintype "passive"))
    )
    (net (code "55") (name "PREL0") (class "Default")
      (node (ref "IC1") (pin "39") (pinfunction "PB3_39") (pintype "bidirectional"))
      (node (ref "Q1") (pin "1") (pinfunction "G_1") (pintype "passive"))
      (node (ref "R2") (pin "1") (pinfunction "1_1") (pintype "passive"))
    )
    (net (code "56") (name "PREL1") (class "Default")
      (node (ref "IC1") (pin "40") (pinfunction "PB4_40") (pintype "bidirectional"))
      (node (ref "Q2") (pin "1") (pinfunction "G_1") (pintype "passive"))
      (node (ref "R3") (pin "1") (pinfunction "1_1") (pintype "passive"))
    )
    (net (code "57") (name "PREL2") (class "Default")
      (node (ref "IC1") (pin "41") (pinfunction "PB5_41") (pintype "bidirectional"))
      (node (ref "Q3") (pin "1") (pinfunction "G_1") (pintype "passive"))
      (node (ref "R4") (pin "1") (pinfunction "1_1") (pintype "passive"))
    )
    (net (code "58") (name "PREL3") (class "Default")
      (node (ref "IC1") (pin "42") (pinfunction "PB6_42") (pintype "bidirectional"))
      (node (ref "Q4") (pin "1") (pinfunction "G_1") (pintype "passive"))
      (node (ref "R5") (pin "1") (pinfunction "1_1") (pintype "passive"))
    )
    (net (code "59") (name "PREL4") (class "Default")
      (node (ref "IC1") (pin "43") (pinfunction "PB7_43") (pintype "bidirectional"))
      (node (ref "Q5") (pin "1") (pinfunction "G_1") (pintype "passive"))
      (node (ref "R6") (pin "1") (pinfunction "1_1") (pintype "passive"))
    )
    (net (code "60") (name "PREL5") (class "Default")
      (node (ref "IC1") (pin "45") (pinfunction "PB8_45") (pintype "bidirectional"))
      (node (ref "Q6") (pin "1") (pinfunction "G_1") (pintype "passive"))
      (node (ref "R7") (pin "1") (pinfunction "1_1") (pintype "passive"))
    )
    (net (code "61") (name "SWCLK") (class "Default")
      (node (ref "IC1") (pin "37") (pinfunction "PA14_37") (pintype "bidirectional"))
      (node (ref "X1") (pin "2") (pinfunction "1_2") (pintype "passive"))
    )
    (net (code "62") (name "SWDIO") (class "Default")
      (node (ref "IC1") (pin "34") (pinfunction "PA13_34") (pintype "bidirectional"))
      (node (ref "X1") (pin "4") (pinfunction "1_4") (pintype "passive"))
    )
    (net (code "63") (name "UART_RX") (class "Default")
      (node (ref "IC1") (pin "31") (pinfunction "PA10_31") (pintype "bidirectional"))
      (node (ref "X2") (pin "28") (pinfunction "1_28") (pintype "passive"))
    )
    (net (code "64") (name "UART_TX") (class "Default")
      (node (ref "IC1") (pin "30") (pinfunction "PA9_30") (pintype "bidirectional"))
      (node (ref "IC2") (pin "2") (pinfunction "I_2") (pintype "input"))
      (node (ref "RN2") (pin "1") (pinfunction "1_1") (pintype "passive"))
    )
    (net (code "65") (name "unconnected-(IC1-PA0-Pad10)") (class "Default")
      (node (ref "IC1") (pin "10") (pinfunction "PA0_10") (pintype "bidirectional"))
    )
    (net (code "66") (name "unconnected-(IC1-PA1-Pad11)") (class "Default")
      (node (ref "IC1") (pin "11") (pinfunction "PA1_11") (pintype "bidirectional"))
    )
    (net (code "67") (name "unconnected-(IC1-PA2-Pad12)") (class "Default")
      (node (ref "IC1") (pin "12") (pinfunction "PA2_12") (pintype "bidirectional"))
    )
    (net (code "68") (name "unconnected-(IC1-PA3-Pad13)") (class "Default")
      (node (ref "IC1") (pin "13") (pinfunction "PA3_13") (pintype "bidirectional"))
    )
    (net (code "69") (name "unconnected-(IC1-PA4-Pad14)") (class "Default")
      (node (ref "IC1") (pin "14") (pinfunction "PA4_14") (pintype "bidirectional"))
    )
    (net (code "70") (name "unconnected-(IC1-PA5-Pad15)") (class "Default")
      (node (ref "IC1") (pin "15") (pinfunction "PA5_15") (pintype "bidirectional"))
    )
    (net (code "71") (name "unconnected-(IC1-PA6-Pad16)") (class "Default")
      (node (ref "IC1") (pin "16") (pinfunction "PA6_16") (pintype "bidirectional"))
    )
    (net (code "72") (name "unconnected-(IC1-PA7-Pad17)") (class "Default")
      (node (ref "IC1") (pin "17") (pinfunction "PA7_17") (pintype "bidirectional"))
    )
    (net (code "73") (name "unconnected-(IC1-PA8-Pad29)") (class "Default")
      (node (ref "IC1") (pin "29") (pinfunction "PA8_29") (pintype "bidirectional"))
    )
    (net (code "74") (name "unconnected-(IC1-PA11-Pad32)") (class "Default")
      (node (ref "IC1") (pin "32") (pinfunction "PA11_32") (pintype "bidirectional"))
    )
    (net (code "75") (name "unconnected-(IC1-PA15-Pad38)") (class "Default")
      (node (ref "IC1") (pin "38") (pinfunction "PA15_38") (pintype "bidirectional"))
    )
    (net (code "76") (name "unconnected-(IC1-PB0-Pad18)") (class "Default")
      (node (ref "IC1") (pin "18") (pinfunction "PB0_18") (pintype "bidirectional"))
    )
    (net (code "77") (name "unconnected-(IC1-PB1-Pad19)") (class "Default")
      (node (ref "IC1") (pin "19") (pinfunction "PB1_19") (pintype "bidirectional"))
    )
    (net (code "78") (name "unconnected-(IC1-PB2-Pad20)") (class "Default")
      (node (ref "IC1") (pin "20") (pinfunction "PB2_20") (pintype "bidirectional"))
    )
    (net (code "79") (name "unconnected-(IC1-PB9-Pad46)") (class "Default")
      (node (ref "IC1") (pin "46") (pinfunction "PB9_46") (pintype "bidirectional"))
    )
    (net (code "80") (name "unconnected-(IC1-PB10-Pad21)") (class "Default")
      (node (ref "IC1") (pin "21") (pinfunction "PB10_21") (pintype "bidirectional"))
    )
    (net (code "81") (name "unconnected-(IC1-PB11-Pad22)") (class "Default")
      (node (ref "IC1") (pin "22") (pinfunction "PB11_22") (pintype "bidirectional"))
    )
    (net (code "82") (name "unconnected-(IC1-PC13-Pad2)") (class "Default")
      (node (ref "IC1") (pin "2") (pinfunction "PC13_2") (pintype "bidirectional"))
    )
    (net (code "83") (name "unconnected-(IC1-PC14-OSC32_IN-Pad3)") (class "Default")
      (node (ref "IC1") (pin "3") (pinfunction "PC14-OSC32_IN_3") (pintype "bidirectional"))
    )
    (net (code "84") (name "unconnected-(IC1-PC15-OSC32_OUT-Pad4)") (class "Default")
      (node (ref "IC1") (pin "4") (pinfunction "PC15-OSC32_OUT_4") (pintype "bidirectional"))
    )
    (net (code "85") (name "unconnected-(IC1-PF0-OSC_IN-Pad5)") (class "Default")
      (node (ref "IC1") (pin "5") (pinfunction "PF0-OSC_IN_5") (pintype "bidirectional"))
    )
    (net (code "86") (name "unconnected-(IC1-PF1-OSC_OUT-Pad6)") (class "Default")
      (node (ref "IC1") (pin "6") (pinfunction "PF1-OSC_OUT_6") (pintype "bidirectional"))
    )
    (net (code "87") (name "unconnected-(IC1-PF6-Pad35)") (class "Default")
      (node (ref "IC1") (pin "35") (pinfunction "PF6_35") (pintype "bidirectional"))
    )
    (net (code "88") (name "unconnected-(IC1-PF7-Pad36)") (class "Default")
      (node (ref "IC1") (pin "36") (pinfunction "PF7_36") (pintype "bidirectional"))
    )
    (net (code "89") (name "unconnected-(K1A-S-Pad12A)") (class "Default")
      (node (ref "K1") (pin "12A") (pinfunction "S_12A") (pintype "passive"))
    )
    (net (code "90") (name "unconnected-(K1B-S-Pad12B)") (class "Default")
      (node (ref "K1") (pin "12B") (pinfunction "S_12B") (pintype "passive"))
    )
    (net (code "91") (name "unconnected-(K6A-S-Pad12A)") (class "Default")
      (node (ref "K6") (pin "12A") (pinfunction "S_12A") (pintype "passive"))
    )
    (net (code "92") (name "unconnected-(K6B-S-Pad12B)") (class "Default")
      (node (ref "K6") (pin "12B") (pinfunction "S_12B") (pintype "passive"))
    )
    (net (code "93") (name "unconnected-(X2-Pad1)") (class "Default")
      (node (ref "X2") (pin "1") (pinfunction "1_1") (pintype "passive"))
    )
    (net (code "94") (name "unconnected-(X2L-1-Pad2)") (class "Default")
      (node (ref "X2") (pin "2") (pinfunction "1_2") (pintype "passive"))
    )
    (net (code "95") (name "unconnected-(X2V-1-Pad3)") (class "Default")
      (node (ref "X2") (pin "3") (pinfunction "1_3") (pintype "passive"))
    )
    (net (code "96") (name "unconnected-(X2Y-1-Pad6)") (class "Default")
      (node (ref "X2") (pin "6") (pinfunction "1_6") (pintype "passive"))
    )
  )
)
